# main.net
KiCad netlist of a schematic drawn in Altium Designer
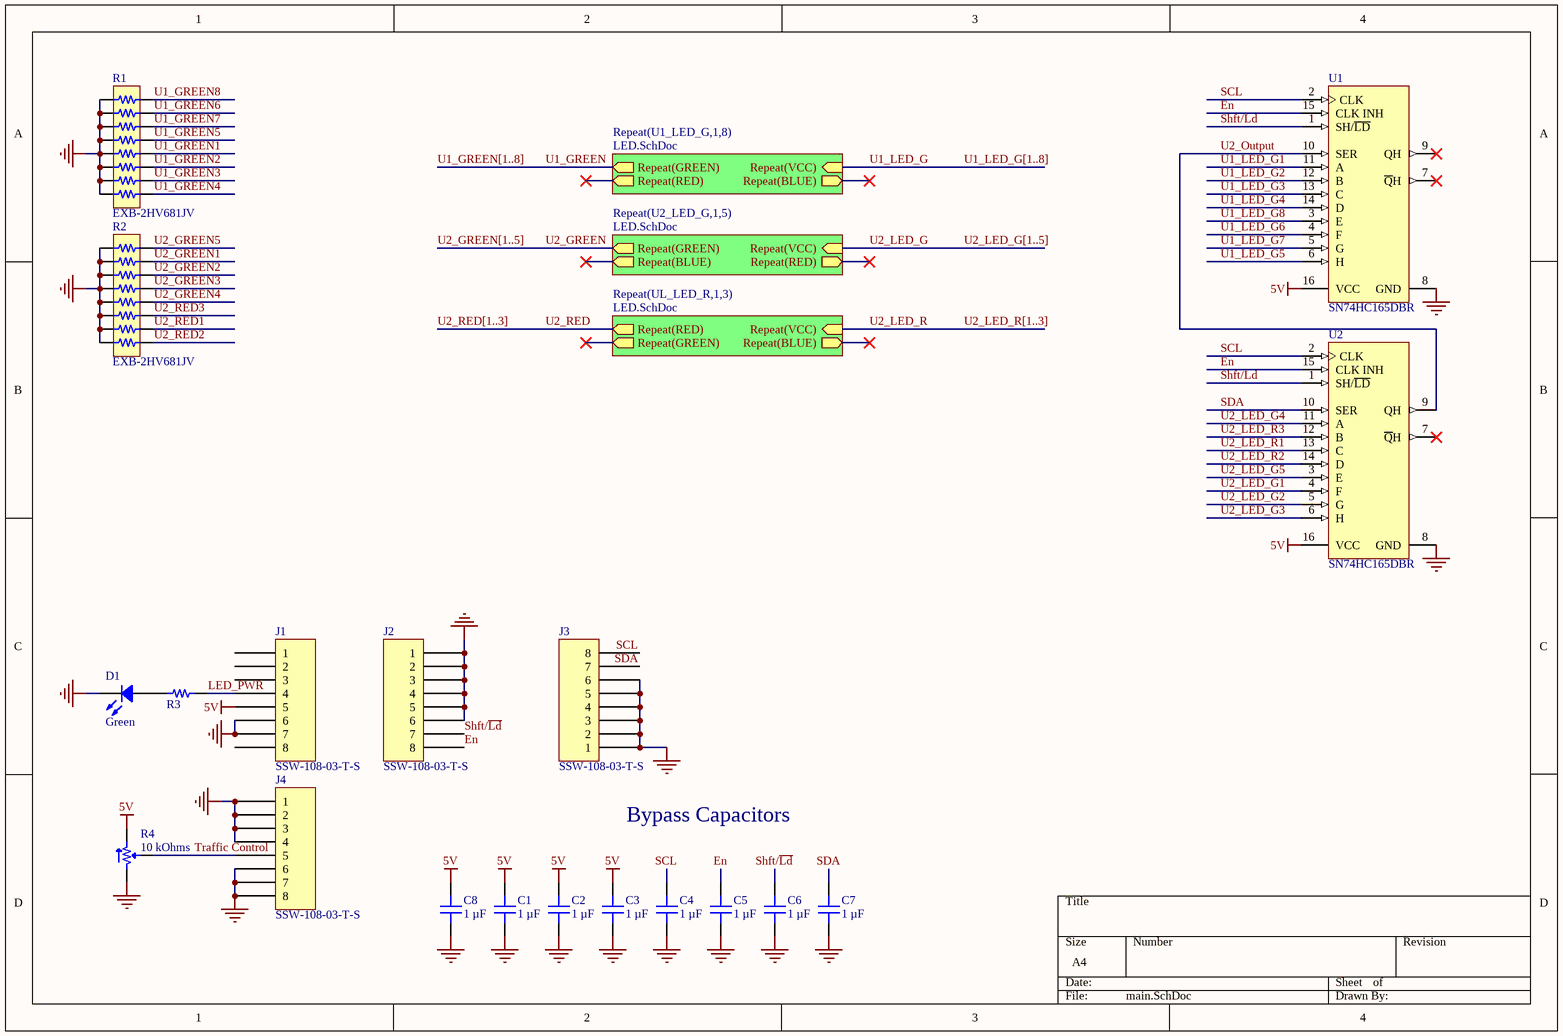
[diagram p0: main.SchDoc]

(export (version "E")
  (design (tool "Eeschema 10.0.6"))
  (components
    (comp (ref "C1")
      (value "1 µF")
      (footprint "CAP 0805_2012")
      (description "CAP CER 1UF 10V X7R 0805")
      (fields (field (name "PART NUMBER") "885012207022") (field (name "MANUFACTURER") "Würth Elektronik"))
      (libsource (lib "Celestial Altium Library - altium_library") (part "Capacitor"))
    )
    (comp (ref "C2")
      (value "1 µF")
      (footprint "CAP 0805_2012")
      (description "CAP CER 1UF 10V X7R 0805")
      (fields (field (name "PART NUMBER") "885012207022") (field (name "MANUFACTURER") "Würth Elektronik"))
      (libsource (lib "Celestial Altium Library - altium_library") (part "Capacitor"))
    )
    (comp (ref "C3")
      (value "1 µF")
      (footprint "CAP 0805_2012")
      (description "CAP CER 1UF 10V X7R 0805")
      (fields (field (name "PART NUMBER") "885012207022") (field (name "MANUFACTURER") "Würth Elektronik"))
      (libsource (lib "Celestial Altium Library - altium_library") (part "Capacitor"))
    )
    (comp (ref "C4")
      (value "1 µF")
      (footprint "CAP 0805_2012")
      (description "CAP CER 1UF 10V X7R 0805")
      (fields (field (name "PART NUMBER") "885012207022") (field (name "MANUFACTURER") "Würth Elektronik"))
      (libsource (lib "Celestial Altium Library - altium_library") (part "Capacitor"))
    )
    (comp (ref "C5")
      (value "1 µF")
      (footprint "CAP 0805_2012")
      (description "CAP CER 1UF 10V X7R 0805")
      (fields (field (name "PART NUMBER") "885012207022") (field (name "MANUFACTURER") "Würth Elektronik"))
      (libsource (lib "Celestial Altium Library - altium_library") (part "Capacitor"))
    )
    (comp (ref "C6")
      (value "1 µF")
      (footprint "CAP 0805_2012")
      (description "CAP CER 1UF 10V X7R 0805")
      (fields (field (name "PART NUMBER") "885012207022") (field (name "MANUFACTURER") "Würth Elektronik"))
      (libsource (lib "Celestial Altium Library - altium_library") (part "Capacitor"))
    )
    (comp (ref "C7")
      (value "1 µF")
      (footprint "CAP 0805_2012")
      (description "CAP CER 1UF 10V X7R 0805")
      (fields (field (name "PART NUMBER") "885012207022") (field (name "MANUFACTURER") "Würth Elektronik"))
      (libsource (lib "Celestial Altium Library - altium_library") (part "Capacitor"))
    )
    (comp (ref "C8")
      (value "1 µF")
      (footprint "CAP 0805_2012")
      (description "CAP CER 1UF 10V X7R 0805")
      (fields (field (name "PART NUMBER") "885012207022") (field (name "MANUFACTURER") "Würth Elektronik"))
      (libsource (lib "Celestial Altium Library - altium_library") (part "Capacitor"))
    )
    (comp (ref "D1")
      (value "Green")
      (footprint "LED 0805_2012 GREEN")
      (description "LED GREEN CLEAR CHIP SMD")
      (fields (field (name "PART NUMBER") "XZVG54W-1") (field (name "MANUFACTURER") "SunLED"))
      (libsource (lib "Celestial Altium Library - altium_library") (part "LED"))
    )
    (comp (ref "J1")
      (value "SSW-108-03-T-S")
      (footprint "SAMTEC SSW-108-03-T-S")
      (description "CONN RCPT 8POS 0.1 TIN PCB")
      (fields (field (name "MANUFACTURER") "Samtec Inc."))
      (libsource (lib "Celestial Altium Library - altium_library") (part "8 Pin"))
    )
    (comp (ref "J2")
      (value "SSW-108-03-T-S")
      (footprint "SAMTEC SSW-108-03-T-S")
      (description "CONN RCPT 8POS 0.1 TIN PCB")
      (fields (field (name "MANUFACTURER") "Samtec Inc."))
      (libsource (lib "") (part "8 Pin_1"))
    )
    (comp (ref "J3")
      (value "SSW-108-03-T-S")
      (footprint "SAMTEC SSW-108-03-T-S")
      (description "CONN RCPT 8POS 0.1 TIN PCB")
      (fields (field (name "MANUFACTURER") "Samtec Inc."))
      (libsource (lib "") (part "8 Pin_2"))
    )
    (comp (ref "J4")
      (value "SSW-108-03-T-S")
      (footprint "SAMTEC SSW-108-03-T-S")
      (description "CONN RCPT 8POS 0.1 TIN PCB")
      (fields (field (name "MANUFACTURER") "Samtec Inc."))
      (libsource (lib "Celestial Altium Library - altium_library") (part "8 Pin"))
    )
    (comp (ref "R1")
      (value "EXB-2HV681JV")
      (footprint "RESNET 1506-16 CONVEX")
      (description "RES ARRAY 8 RES 680 OHM 1506")
      (fields
        (field (name "MANUFACTURER") "Panasonic Electronic Components")
        (field (name "TOLERANCE") "±5%")
      )
      (libsource (lib "Celestial Altium Library - altium_library") (part "Resistor Array (8 Circuit)"))
    )
    (comp (ref "R2")
      (value "EXB-2HV681JV")
      (footprint "RESNET 1506-16 CONVEX")
      (description "RES ARRAY 8 RES 680 OHM 1506")
      (fields
        (field (name "MANUFACTURER") "Panasonic Electronic Components")
        (field (name "TOLERANCE") "±5%")
      )
      (libsource (lib "Celestial Altium Library - altium_library") (part "Resistor Array (8 Circuit)"))
    )
    (comp (ref "R3")
      (value "0 Ohms")
      (footprint "RES 0805_2012")
      (description "RESA-AS 0805 0R JUMPER 125MW")
      (fields (field (name "PART NUMBER") "CR0805AJ/-000EAS") (field (name "MANUFACTURER") "Bourns Inc."))
      (libsource (lib "Celestial Altium Library - altium_library") (part "Resistor"))
    )
    (comp (ref "R4")
      (value "10 kOhms")
      (footprint "BOURNS TRIMPOT 3362P-1")
      (description "TRIMMER 10K OHM 0.5W PC PIN TOP")
      (fields (field (name "PART NUMBER") "3362P-1-103LF") (field (name "MANUFACTURER") "Bourns Inc."))
      (libsource (lib "Celestial Altium Library - altium_library") (part "Potentiometer"))
    )
    (comp (ref "U1")
      (value "SN74HC165DBR")
      (footprint "DB0016A_N")
      (description "8-Bit Parallel-Load Shift Registers, DB0016A, LARGE T&R")
      (fields
        (field (name "GENERIC PART NUMBER") "SN74HC165")
        (field (name "MANUFACTURER") "Texas Instruments")
      )
      (libsource (lib "Altium Content Vault") (part "TI-SNX4XXX165X-16"))
    )
    (comp (ref "U2")
      (value "SN74HC165DBR")
      (footprint "DB0016A_N")
      (description "8-Bit Parallel-Load Shift Registers, DB0016A, LARGE T&R")
      (fields
        (field (name "GENERIC PART NUMBER") "SN74HC165")
        (field (name "MANUFACTURER") "Texas Instruments")
      )
      (libsource (lib "Altium Content Vault") (part "TI-SNX4XXX165X-16"))
    )
  )
  (nets
    (net (code "2") (name "/En") (class "Default")
      (node (ref "C5") (pin "2") (pinfunction "2_2") (pintype "passive"))
      (node (ref "J2") (pin "8") (pinfunction "8_8") (pintype "passive"))
      (node (ref "U1") (pin "15") (pinfunction "CLK_INH_15") (pintype "input"))
      (node (ref "U2") (pin "15") (pinfunction "CLK_INH_15") (pintype "input"))
    )
    (net (code "3") (name "/LED_PWR") (class "Default")
      (node (ref "J1") (pin "4") (pinfunction "4_4") (pintype "passive"))
      (node (ref "R3") (pin "1") (pinfunction "1_1") (pintype "passive"))
    )
    (net (code "10") (name "/SCL") (class "Default")
      (node (ref "C4") (pin "2") (pinfunction "2_2") (pintype "passive"))
      (node (ref "J3") (pin "8") (pinfunction "8_8") (pintype "passive"))
      (node (ref "U1") (pin "2") (pinfunction "CLK_2") (pintype "input"))
      (node (ref "U2") (pin "2") (pinfunction "CLK_2") (pintype "input"))
    )
    (net (code "11") (name "/SDA") (class "Default")
      (node (ref "C7") (pin "2") (pinfunction "2_2") (pintype "passive"))
      (node (ref "J3") (pin "7") (pinfunction "7_7") (pintype "passive"))
      (node (ref "U2") (pin "10") (pinfunction "SER_10") (pintype "input"))
    )
    (net (code "12") (name "/Shft{slash}~{Ld}") (class "Default")
      (node (ref "C6") (pin "2") (pinfunction "2_2") (pintype "passive"))
      (node (ref "J2") (pin "7") (pinfunction "7_7") (pintype "passive"))
      (node (ref "U1") (pin "1") (pinfunction "SH/~{LD}_1") (pintype "input"))
      (node (ref "U2") (pin "1") (pinfunction "SH/~{LD}_1") (pintype "input"))
    )
    (net (code "13") (name "/Traffic Control") (class "Default")
      (node (ref "J4") (pin "5") (pinfunction "5_5") (pintype "passive"))
      (node (ref "R4") (pin "2") (pinfunction "2_2") (pintype "passive"))
    )
    (net (code "15") (name "/U1_GREEN1") (class "Default")
      (node (ref "R1") (pin "12") (pinfunction "12_12") (pintype "passive"))
    )
    (net (code "16") (name "/U1_GREEN2") (class "Default")
      (node (ref "R1") (pin "11") (pinfunction "11_11") (pintype "passive"))
    )
    (net (code "17") (name "/U1_GREEN3") (class "Default")
      (node (ref "R1") (pin "10") (pinfunction "10_10") (pintype "passive"))
    )
    (net (code "18") (name "/U1_GREEN4") (class "Default")
      (node (ref "R1") (pin "9") (pinfunction "9_9") (pintype "passive"))
    )
    (net (code "19") (name "/U1_GREEN5") (class "Default")
      (node (ref "R1") (pin "13") (pinfunction "13_13") (pintype "passive"))
    )
    (net (code "20") (name "/U1_GREEN6") (class "Default")
      (node (ref "R1") (pin "15") (pinfunction "15_15") (pintype "passive"))
    )
    (net (code "21") (name "/U1_GREEN7") (class "Default")
      (node (ref "R1") (pin "14") (pinfunction "14_14") (pintype "passive"))
    )
    (net (code "22") (name "/U1_GREEN8") (class "Default")
      (node (ref "R1") (pin "16") (pinfunction "16_16") (pintype "passive"))
    )
    (net (code "25") (name "/U1_LED_G1") (class "Default")
      (node (ref "U1") (pin "11") (pinfunction "A_11") (pintype "input"))
    )
    (net (code "26") (name "/U1_LED_G2") (class "Default")
      (node (ref "U1") (pin "12") (pinfunction "B_12") (pintype "input"))
    )
    (net (code "27") (name "/U1_LED_G3") (class "Default")
      (node (ref "U1") (pin "13") (pinfunction "C_13") (pintype "input"))
    )
    (net (code "28") (name "/U1_LED_G4") (class "Default")
      (node (ref "U1") (pin "14") (pinfunction "D_14") (pintype "input"))
    )
    (net (code "29") (name "/U1_LED_G5") (class "Default")
      (node (ref "U1") (pin "6") (pinfunction "H_6") (pintype "input"))
    )
    (net (code "30") (name "/U1_LED_G6") (class "Default")
      (node (ref "U1") (pin "4") (pinfunction "F_4") (pintype "input"))
    )
    (net (code "31") (name "/U1_LED_G7") (class "Default")
      (node (ref "U1") (pin "5") (pinfunction "G_5") (pintype "input"))
    )
    (net (code "32") (name "/U1_LED_G8") (class "Default")
      (node (ref "U1") (pin "3") (pinfunction "E_3") (pintype "input"))
    )
    (net (code "35") (name "/U2_GREEN1") (class "Default")
      (node (ref "R2") (pin "15") (pinfunction "15_15") (pintype "passive"))
    )
    (net (code "36") (name "/U2_GREEN2") (class "Default")
      (node (ref "R2") (pin "14") (pinfunction "14_14") (pintype "passive"))
    )
    (net (code "37") (name "/U2_GREEN3") (class "Default")
      (node (ref "R2") (pin "13") (pinfunction "13_13") (pintype "passive"))
    )
    (net (code "38") (name "/U2_GREEN4") (class "Default")
      (node (ref "R2") (pin "12") (pinfunction "12_12") (pintype "passive"))
    )
    (net (code "39") (name "/U2_GREEN5") (class "Default")
      (node (ref "R2") (pin "16") (pinfunction "16_16") (pintype "passive"))
    )
    (net (code "42") (name "/U2_LED_G1") (class "Default")
      (node (ref "U2") (pin "4") (pinfunction "F_4") (pintype "input"))
    )
    (net (code "43") (name "/U2_LED_G2") (class "Default")
      (node (ref "U2") (pin "5") (pinfunction "G_5") (pintype "input"))
    )
    (net (code "44") (name "/U2_LED_G3") (class "Default")
      (node (ref "U2") (pin "6") (pinfunction "H_6") (pintype "input"))
    )
    (net (code "45") (name "/U2_LED_G4") (class "Default")
      (node (ref "U2") (pin "11") (pinfunction "A_11") (pintype "input"))
    )
    (net (code "46") (name "/U2_LED_G5") (class "Default")
      (node (ref "U2") (pin "3") (pinfunction "E_3") (pintype "input"))
    )
    (net (code "49") (name "/U2_LED_R1") (class "Default")
      (node (ref "U2") (pin "13") (pinfunction "C_13") (pintype "input"))
    )
    (net (code "50") (name "/U2_LED_R2") (class "Default")
      (node (ref "U2") (pin "14") (pinfunction "D_14") (pintype "input"))
    )
    (net (code "51") (name "/U2_LED_R3") (class "Default")
      (node (ref "U2") (pin "12") (pinfunction "B_12") (pintype "input"))
    )
    (net (code "53") (name "/U2_Output") (class "Default")
      (node (ref "U1") (pin "10") (pinfunction "SER_10") (pintype "input"))
      (node (ref "U2") (pin "9") (pinfunction "QH_9") (pintype "output"))
    )
    (net (code "55") (name "/U2_RED1") (class "Default")
      (node (ref "R2") (pin "10") (pinfunction "10_10") (pintype "passive"))
    )
    (net (code "56") (name "/U2_RED2") (class "Default")
      (node (ref "R2") (pin "9") (pinfunction "9_9") (pintype "passive"))
    )
    (net (code "57") (name "/U2_RED3") (class "Default")
      (node (ref "R2") (pin "11") (pinfunction "11_11") (pintype "passive"))
    )
    (net (code "59") (name "5V") (class "Default")
      (node (ref "C1") (pin "2") (pinfunction "2_2") (pintype "passive"))
      (node (ref "C2") (pin "2") (pinfunction "2_2") (pintype "passive"))
      (node (ref "C3") (pin "2") (pinfunction "2_2") (pintype "passive"))
      (node (ref "C8") (pin "2") (pinfunction "2_2") (pintype "passive"))
      (node (ref "J1") (pin "5") (pinfunction "5_5") (pintype "passive"))
      (node (ref "R4") (pin "3") (pinfunction "3_3") (pintype "passive"))
      (node (ref "U1") (pin "16") (pinfunction "VCC_16") (pintype "power_in"))
      (node (ref "U2") (pin "16") (pinfunction "VCC_16") (pintype "power_in"))
    )
    (net (code "60") (name "GND") (class "Default")
      (node (ref "C1") (pin "1") (pinfunction "1_1") (pintype "passive"))
      (node (ref "C2") (pin "1") (pinfunction "1_1") (pintype "passive"))
      (node (ref "C3") (pin "1") (pinfunction "1_1") (pintype "passive"))
      (node (ref "C4") (pin "1") (pinfunction "1_1") (pintype "passive"))
      (node (ref "C5") (pin "1") (pinfunction "1_1") (pintype "passive"))
      (node (ref "C6") (pin "1") (pinfunction "1_1") (pintype "passive"))
      (node (ref "C7") (pin "1") (pinfunction "1_1") (pintype "passive"))
      (node (ref "C8") (pin "1") (pinfunction "1_1") (pintype "passive"))
      (node (ref "D1") (pin "2") (pinfunction "2_2") (pintype "passive"))
      (node (ref "J1") (pin "6") (pinfunction "6_6") (pintype "passive"))
      (node (ref "J1") (pin "7") (pinfunction "7_7") (pintype "passive"))
      (node (ref "J2") (pin "1") (pinfunction "1_1") (pintype "passive"))
      (node (ref "J2") (pin "2") (pinfunction "2_2") (pintype "passive"))
      (node (ref "J2") (pin "3") (pinfunction "3_3") (pintype "passive"))
      (node (ref "J2") (pin "4") (pinfunction "4_4") (pintype "passive"))
      (node (ref "J2") (pin "5") (pinfunction "5_5") (pintype "passive"))
      (node (ref "J2") (pin "6") (pinfunction "6_6") (pintype "passive"))
      (node (ref "J3") (pin "1") (pinfunction "1_1") (pintype "passive"))
      (node (ref "J3") (pin "2") (pinfunction "2_2") (pintype "passive"))
      (node (ref "J3") (pin "3") (pinfunction "3_3") (pintype "passive"))
      (node (ref "J3") (pin "4") (pinfunction "4_4") (pintype "passive"))
      (node (ref "J3") (pin "5") (pinfunction "5_5") (pintype "passive"))
      (node (ref "J3") (pin "6") (pinfunction "6_6") (pintype "passive"))
      (node (ref "J4") (pin "1") (pinfunction "1_1") (pintype "passive"))
      (node (ref "J4") (pin "2") (pinfunction "2_2") (pintype "passive"))
      (node (ref "J4") (pin "3") (pinfunction "3_3") (pintype "passive"))
      (node (ref "J4") (pin "4") (pinfunction "4_4") (pintype "passive"))
      (node (ref "J4") (pin "6") (pinfunction "6_6") (pintype "passive"))
      (node (ref "J4") (pin "7") (pinfunction "7_7") (pintype "passive"))
      (node (ref "J4") (pin "8") (pinfunction "8_8") (pintype "passive"))
      (node (ref "R1") (pin "1") (pinfunction "1_1") (pintype "passive"))
      (node (ref "R1") (pin "2") (pinfunction "2_2") (pintype "passive"))
      (node (ref "R1") (pin "3") (pinfunction "3_3") (pintype "passive"))
      (node (ref "R1") (pin "4") (pinfunction "4_4") (pintype "passive"))
      (node (ref "R1") (pin "5") (pinfunction "6_5") (pintype "passive"))
      (node (ref "R1") (pin "6") (pinfunction "6_6") (pintype "passive"))
      (node (ref "R1") (pin "7") (pinfunction "7_7") (pintype "passive"))
      (node (ref "R1") (pin "8") (pinfunction "8_8") (pintype "passive"))
      (node (ref "R2") (pin "1") (pinfunction "1_1") (pintype "passive"))
      (node (ref "R2") (pin "2") (pinfunction "2_2") (pintype "passive"))
      (node (ref "R2") (pin "3") (pinfunction "3_3") (pintype "passive"))
      (node (ref "R2") (pin "4") (pinfunction "4_4") (pintype "passive"))
      (node (ref "R2") (pin "5") (pinfunction "6_5") (pintype "passive"))
      (node (ref "R2") (pin "6") (pinfunction "6_6") (pintype "passive"))
      (node (ref "R2") (pin "7") (pinfunction "7_7") (pintype "passive"))
      (node (ref "R2") (pin "8") (pinfunction "8_8") (pintype "passive"))
      (node (ref "R4") (pin "1") (pinfunction "1_1") (pintype "passive"))
      (node (ref "U1") (pin "8") (pinfunction "GND_8") (pintype "power_in"))
      (node (ref "U2") (pin "8") (pinfunction "GND_8") (pintype "power_in"))
    )
    (net (code "61") (name "Net-(D1-Pad1)") (class "Default")
      (node (ref "D1") (pin "1") (pinfunction "1_1") (pintype "passive"))
      (node (ref "R3") (pin "2") (pinfunction "2_2") (pintype "passive"))
    )
    (net (code "62") (name "unconnected-(J1-Pad1)") (class "Default")
      (node (ref "J1") (pin "1") (pinfunction "1_1") (pintype "passive"))
    )
    (net (code "63") (name "unconnected-(J1-Pad2)") (class "Default")
      (node (ref "J1") (pin "2") (pinfunction "2_2") (pintype "passive"))
    )
    (net (code "64") (name "unconnected-(J1-Pad3)") (class "Default")
      (node (ref "J1") (pin "3") (pinfunction "3_3") (pintype "passive"))
    )
    (net (code "65") (name "unconnected-(J1-Pad8)") (class "Default")
      (node (ref "J1") (pin "8") (pinfunction "8_8") (pintype "passive"))
    )
    (net (code "66") (name "unconnected-(U1-QH-Pad9)") (class "Default")
      (node (ref "U1") (pin "9") (pinfunction "QH_9") (pintype "output+no_connect"))
    )
    (net (code "67") (name "unconnected-(U1-~{Q}H-Pad7)") (class "Default")
      (node (ref "U1") (pin "7") (pinfunction "~{Q}H_7") (pintype "output+no_connect"))
    )
    (net (code "68") (name "unconnected-(U2-~{Q}H-Pad7)") (class "Default")
      (node (ref "U2") (pin "7") (pinfunction "~{Q}H_7") (pintype "output+no_connect"))
    )
  )
)
